# miniDCU.net
KiCad netlist of a schematic drawn in EAGLE
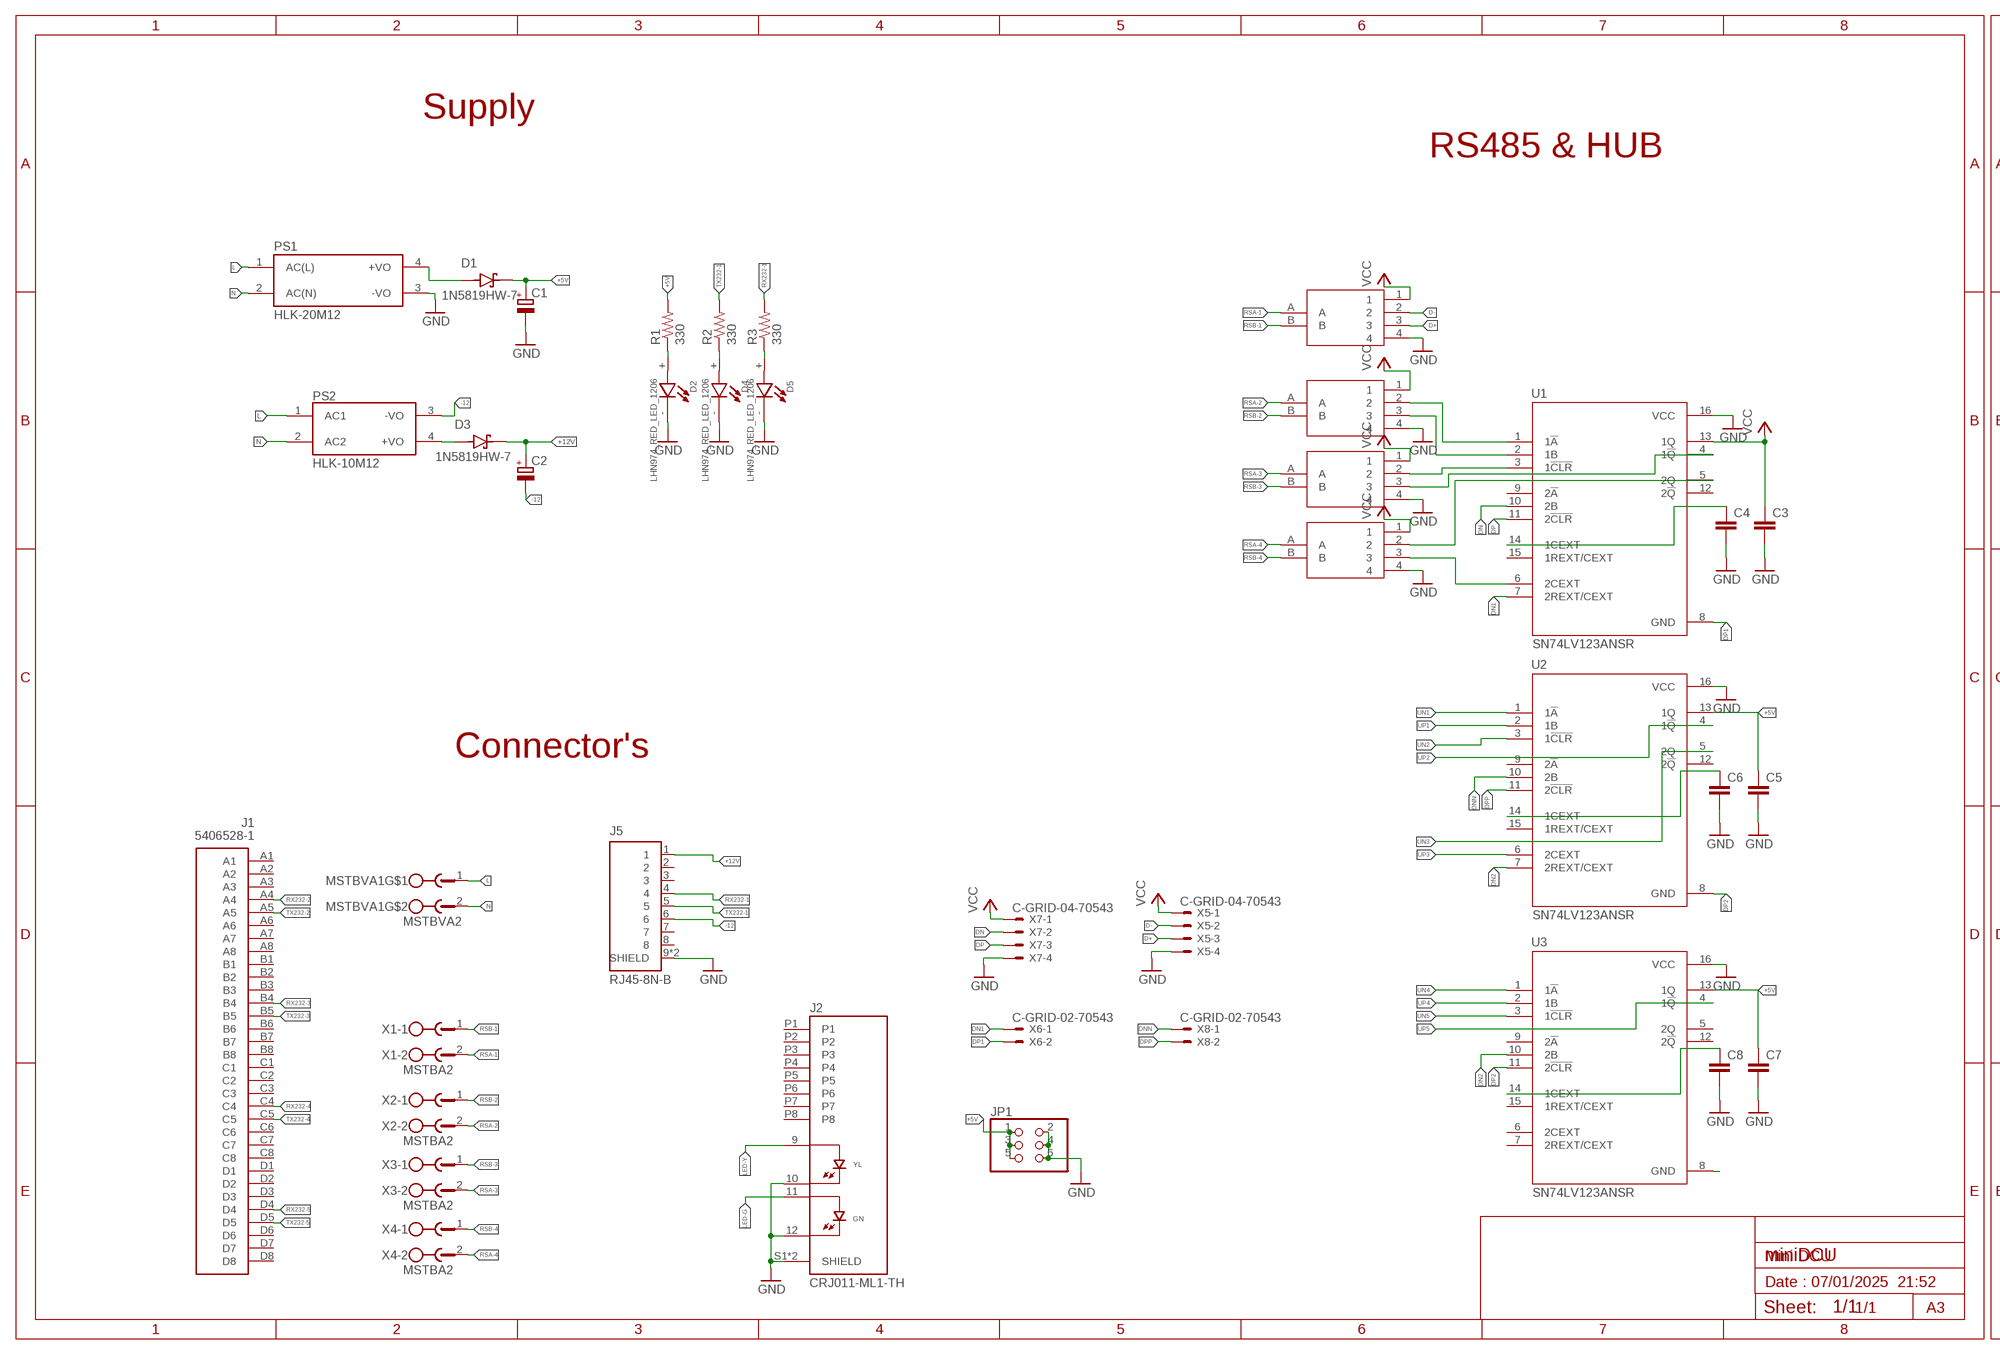
[diagram p0: schematic, sheet 1, part 1 of 2]
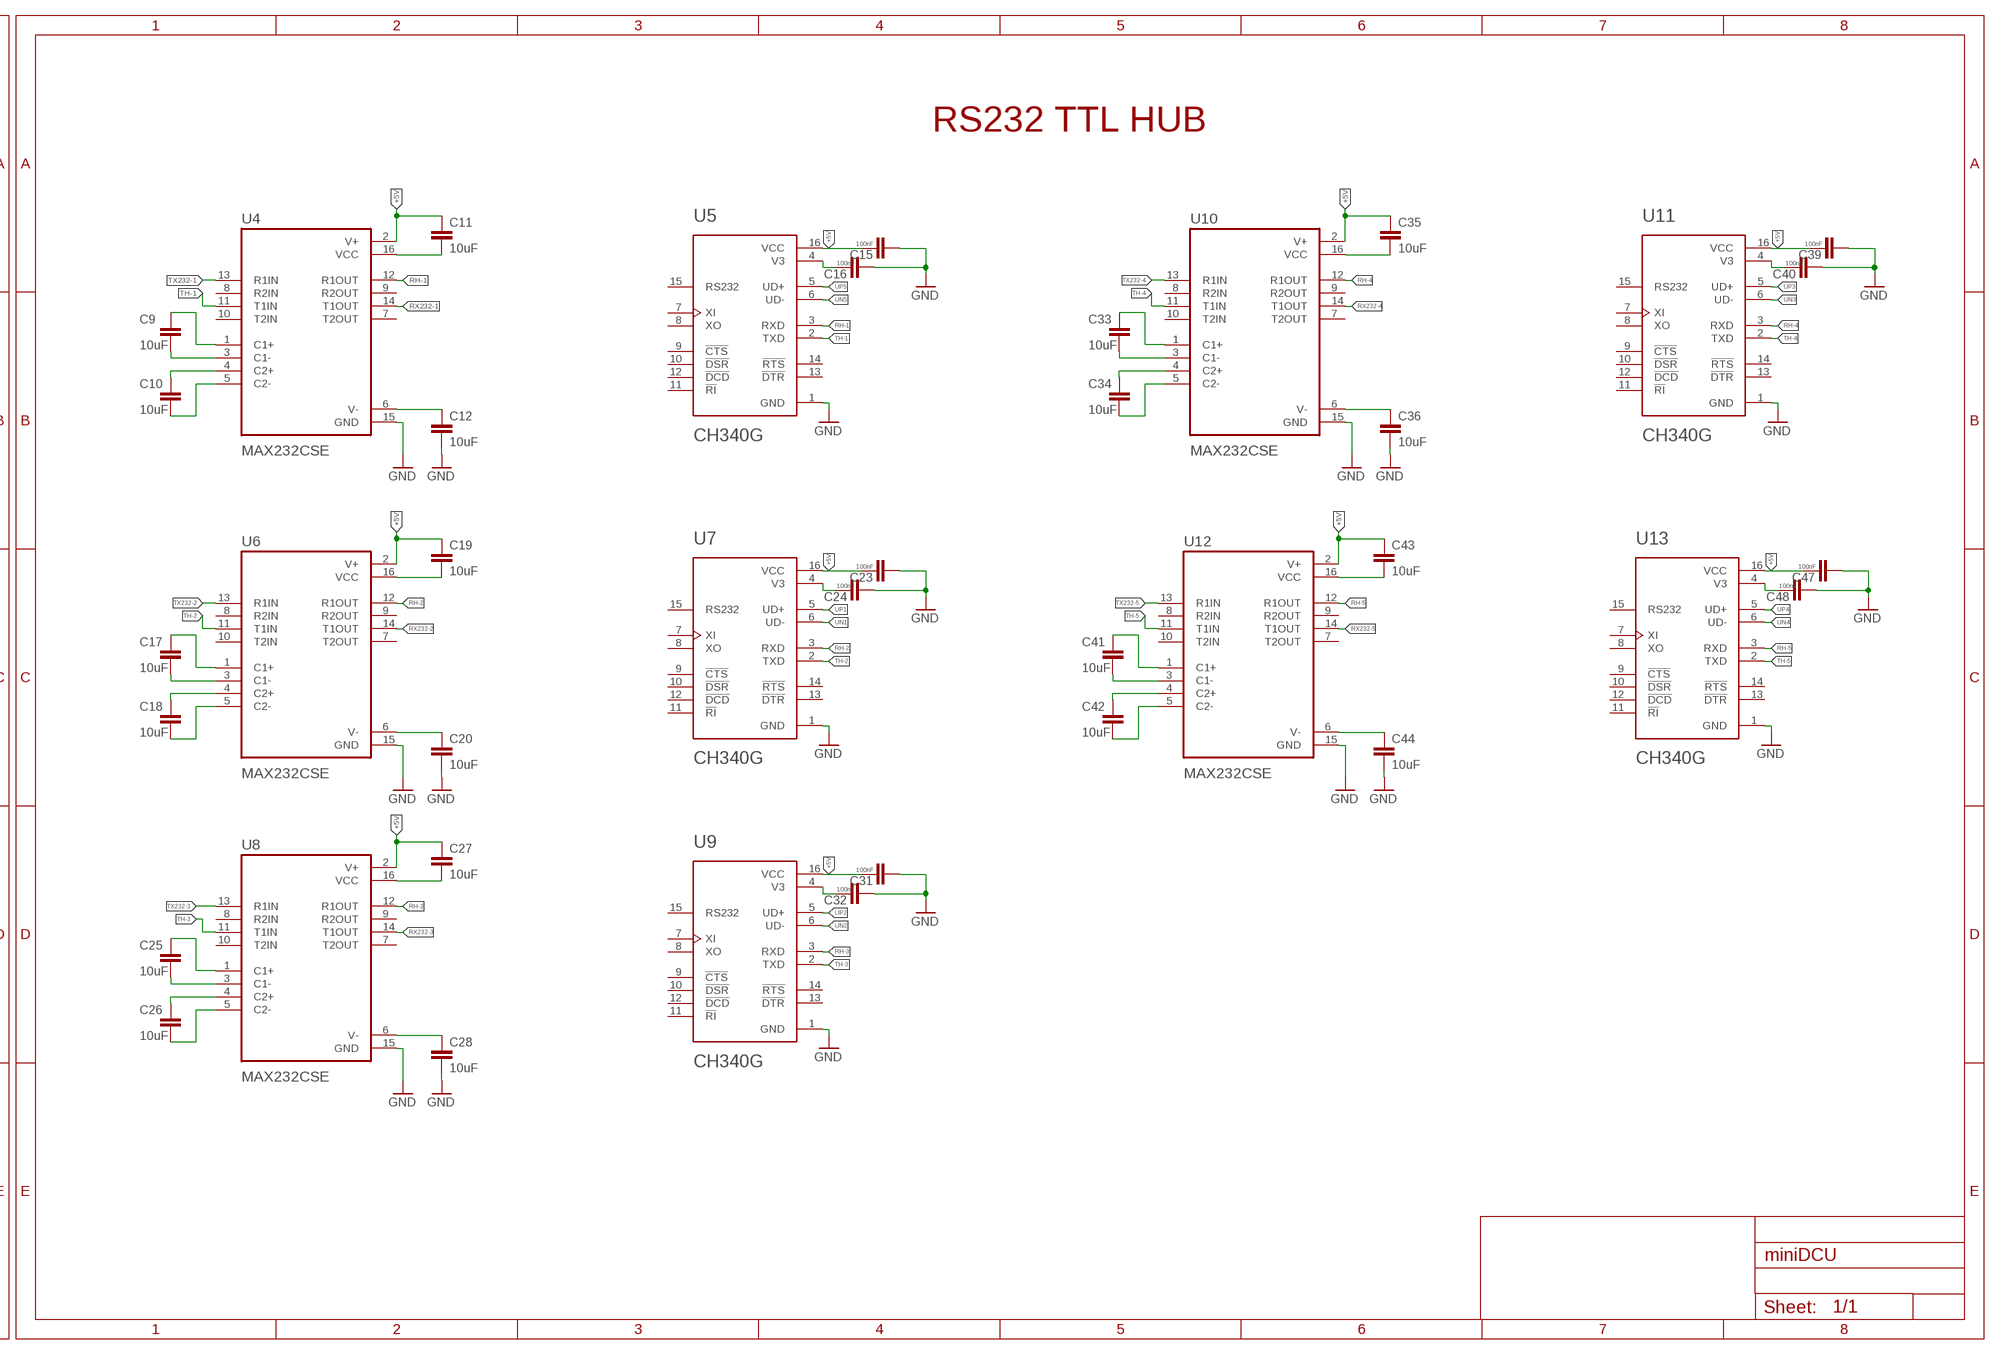
[diagram p1: schematic, sheet 1, part 2 of 2]

(export (version "E")
  (design (tool "Eeschema 10.0.6"))
  (components
    (comp (ref "C1")
      (value "CPOL-EU153CLV-0505")
      (footprint "eagle-import:153CLV-0505")
      (libsource (lib "eagle-import") (part "CPOL-EU153CLV-0505"))
    )
    (comp (ref "C2")
      (value "CPOL-EU153CLV-0505")
      (footprint "eagle-import:153CLV-0505")
      (libsource (lib "eagle-import") (part "CPOL-EU153CLV-0505"))
    )
    (comp (ref "C3")
      (value "C-EUC0603K")
      (footprint "eagle-import:C0603K")
      (libsource (lib "eagle-import") (part "C-EUC0603K"))
    )
    (comp (ref "C4")
      (value "C-EUC0603K")
      (footprint "eagle-import:C0603K")
      (libsource (lib "eagle-import") (part "C-EUC0603K"))
    )
    (comp (ref "C5")
      (value "C-EUC0603K")
      (footprint "eagle-import:C0603K")
      (libsource (lib "eagle-import") (part "C-EUC0603K"))
    )
    (comp (ref "C6")
      (value "C-EUC0603K")
      (footprint "eagle-import:C0603K")
      (libsource (lib "eagle-import") (part "C-EUC0603K"))
    )
    (comp (ref "C7")
      (value "C-EUC0603K")
      (footprint "eagle-import:C0603K")
      (libsource (lib "eagle-import") (part "C-EUC0603K"))
    )
    (comp (ref "C8")
      (value "C-EUC0603K")
      (footprint "eagle-import:C0603K")
      (libsource (lib "eagle-import") (part "C-EUC0603K"))
    )
    (comp (ref "C9")
      (value "10uF")
      (footprint "eagle-import:C0805")
      (libsource (lib "eagle-import") (part "C-EUC0805"))
    )
    (comp (ref "C10")
      (value "10uF")
      (footprint "eagle-import:C0805")
      (libsource (lib "eagle-import") (part "C-EUC0805"))
    )
    (comp (ref "C11")
      (value "10uF")
      (footprint "eagle-import:C0805")
      (libsource (lib "eagle-import") (part "C-EUC0805"))
    )
    (comp (ref "C12")
      (value "10uF")
      (footprint "eagle-import:C0805")
      (libsource (lib "eagle-import") (part "C-EUC0805"))
    )
    (comp (ref "C15")
      (value "100nF")
      (footprint "eagle-import:C0805K")
      (libsource (lib "eagle-import") (part "C-EUC0805K"))
    )
    (comp (ref "C16")
      (value "100nF")
      (footprint "eagle-import:C0805K")
      (libsource (lib "eagle-import") (part "C-EUC0805K"))
    )
    (comp (ref "C17")
      (value "10uF")
      (footprint "eagle-import:C0805")
      (libsource (lib "eagle-import") (part "C-EUC0805"))
    )
    (comp (ref "C18")
      (value "10uF")
      (footprint "eagle-import:C0805")
      (libsource (lib "eagle-import") (part "C-EUC0805"))
    )
    (comp (ref "C19")
      (value "10uF")
      (footprint "eagle-import:C0805")
      (libsource (lib "eagle-import") (part "C-EUC0805"))
    )
    (comp (ref "C20")
      (value "10uF")
      (footprint "eagle-import:C0805")
      (libsource (lib "eagle-import") (part "C-EUC0805"))
    )
    (comp (ref "C23")
      (value "100nF")
      (footprint "eagle-import:C0805K")
      (libsource (lib "eagle-import") (part "C-EUC0805K"))
    )
    (comp (ref "C24")
      (value "100nF")
      (footprint "eagle-import:C0805K")
      (libsource (lib "eagle-import") (part "C-EUC0805K"))
    )
    (comp (ref "C25")
      (value "10uF")
      (footprint "eagle-import:C0805")
      (libsource (lib "eagle-import") (part "C-EUC0805"))
    )
    (comp (ref "C26")
      (value "10uF")
      (footprint "eagle-import:C0805")
      (libsource (lib "eagle-import") (part "C-EUC0805"))
    )
    (comp (ref "C27")
      (value "10uF")
      (footprint "eagle-import:C0805")
      (libsource (lib "eagle-import") (part "C-EUC0805"))
    )
    (comp (ref "C28")
      (value "10uF")
      (footprint "eagle-import:C0805")
      (libsource (lib "eagle-import") (part "C-EUC0805"))
    )
    (comp (ref "C31")
      (value "100nF")
      (footprint "eagle-import:C0805K")
      (libsource (lib "eagle-import") (part "C-EUC0805K"))
    )
    (comp (ref "C32")
      (value "100nF")
      (footprint "eagle-import:C0805K")
      (libsource (lib "eagle-import") (part "C-EUC0805K"))
    )
    (comp (ref "C33")
      (value "10uF")
      (footprint "eagle-import:C0805")
      (libsource (lib "eagle-import") (part "C-EUC0805"))
    )
    (comp (ref "C34")
      (value "10uF")
      (footprint "eagle-import:C0805")
      (libsource (lib "eagle-import") (part "C-EUC0805"))
    )
    (comp (ref "C35")
      (value "10uF")
      (footprint "eagle-import:C0805")
      (libsource (lib "eagle-import") (part "C-EUC0805"))
    )
    (comp (ref "C36")
      (value "10uF")
      (footprint "eagle-import:C0805")
      (libsource (lib "eagle-import") (part "C-EUC0805"))
    )
    (comp (ref "C39")
      (value "100nF")
      (footprint "eagle-import:C0805K")
      (libsource (lib "eagle-import") (part "C-EUC0805K"))
    )
    (comp (ref "C40")
      (value "100nF")
      (footprint "eagle-import:C0805K")
      (libsource (lib "eagle-import") (part "C-EUC0805K"))
    )
    (comp (ref "C41")
      (value "10uF")
      (footprint "eagle-import:C0805")
      (libsource (lib "eagle-import") (part "C-EUC0805"))
    )
    (comp (ref "C42")
      (value "10uF")
      (footprint "eagle-import:C0805")
      (libsource (lib "eagle-import") (part "C-EUC0805"))
    )
    (comp (ref "C43")
      (value "10uF")
      (footprint "eagle-import:C0805")
      (libsource (lib "eagle-import") (part "C-EUC0805"))
    )
    (comp (ref "C44")
      (value "10uF")
      (footprint "eagle-import:C0805")
      (libsource (lib "eagle-import") (part "C-EUC0805"))
    )
    (comp (ref "C47")
      (value "100nF")
      (footprint "eagle-import:C0805K")
      (libsource (lib "eagle-import") (part "C-EUC0805K"))
    )
    (comp (ref "C48")
      (value "100nF")
      (footprint "eagle-import:C0805K")
      (libsource (lib "eagle-import") (part "C-EUC0805K"))
    )
    (comp (ref "D1")
      (value "1N5819HW-7")
      (footprint "eagle-import:SOD3715X145N")
      (fields (field (name "MF") "Diodes Inc."))
      (libsource (lib "eagle-import") (part "1N5819HW-7"))
    )
    (comp (ref "D2")
      (value "LHN974_RED_LED_1206")
      (footprint "eagle-import:LEDC3216X120N")
      (fields (field (name "MF") "Osram") (field (name "MP") "LHN974 RED LED 1206"))
      (libsource (lib "eagle-import") (part "LHN974_RED_LED_1206"))
    )
    (comp (ref "D3")
      (value "1N5819HW-7")
      (footprint "eagle-import:SOD3715X145N")
      (fields (field (name "MF") "Diodes Inc."))
      (libsource (lib "eagle-import") (part "1N5819HW-7"))
    )
    (comp (ref "D4")
      (value "LHN974_RED_LED_1206")
      (footprint "eagle-import:LEDC3216X120N")
      (fields (field (name "MF") "Osram") (field (name "MP") "LHN974 RED LED 1206"))
      (libsource (lib "eagle-import") (part "LHN974_RED_LED_1206"))
    )
    (comp (ref "D5")
      (value "LHN974_RED_LED_1206")
      (footprint "eagle-import:LEDC3216X120N")
      (fields (field (name "MF") "Osram") (field (name "MP") "LHN974 RED LED 1206"))
      (libsource (lib "eagle-import") (part "LHN974_RED_LED_1206"))
    )
    (comp (ref "J1")
      (value "5406528-1")
      (footprint "eagle-import:5406528-1")
      (fields (field (name "MF") "TE Connectivity"))
      (libsource (lib "eagle-import") (part "5406528-1"))
    )
    (comp (ref "J2")
      (value "CRJ011-ML1-TH")
      (footprint "eagle-import:CUI_CRJ011-ML1-TH")
      (fields (field (name "MF") "Same Sky"))
      (libsource (lib "eagle-import") (part "CRJ011-ML1-TH"))
    )
    (comp (ref "J5")
      (value "RJ45-8N-B")
      (footprint "eagle-import:TE_RJ45-8N-B")
      (fields (field (name "MF") "TE Connectivity"))
      (libsource (lib "eagle-import") (part "RJ45-8N-B"))
    )
    (comp (ref "JP1")
      (value "PINHD-2X3")
      (footprint "eagle-import:2X03")
      (libsource (lib "eagle-import") (part "PINHD-2X3"))
    )
    (comp (ref "MSTBVA1")
      (value "MSTBVA2")
      (footprint "eagle-import:MSTBVA2")
      (libsource (lib "eagle-import") (part "MSTBVA2"))
    )
    (comp (ref "PS1")
      (value "HLK-20M12")
      (footprint "eagle-import:CONV_HLK-20M12")
      (fields (field (name "MF") "Hi-link"))
      (libsource (lib "eagle-import") (part "HLK-20M12"))
    )
    (comp (ref "PS2")
      (value "HLK-10M12")
      (footprint "eagle-import:CONV_HLK-10M12")
      (fields (field (name "MF") "Hi-link"))
      (libsource (lib "eagle-import") (part "HLK-10M12"))
    )
    (comp (ref "R1")
      (value "330")
      (footprint "eagle-import:M0805")
      (libsource (lib "eagle-import") (part "R-US_M0805"))
    )
    (comp (ref "R2")
      (value "330")
      (footprint "eagle-import:M0805")
      (libsource (lib "eagle-import") (part "R-US_M0805"))
    )
    (comp (ref "R3")
      (value "330")
      (footprint "eagle-import:M0805")
      (libsource (lib "eagle-import") (part "R-US_M0805"))
    )
    (comp (ref "U1")
      (value "SN74LV123ANSR")
      (footprint "eagle-import:SOIC127P780X200-16N")
      (fields (field (name "DIGIKEY_PART_NUMBER") "296-46201-2-ND") (field (name "MF") "Texas Instruments"))
      (libsource (lib "eagle-import") (part "SN74LV123ANSR"))
    )
    (comp (ref "U2")
      (value "SN74LV123ANSR")
      (footprint "eagle-import:SOIC127P780X200-16N")
      (fields (field (name "DIGIKEY_PART_NUMBER") "296-46201-2-ND") (field (name "MF") "Texas Instruments"))
      (libsource (lib "eagle-import") (part "SN74LV123ANSR"))
    )
    (comp (ref "U3")
      (value "SN74LV123ANSR")
      (footprint "eagle-import:SOIC127P780X200-16N")
      (fields (field (name "DIGIKEY_PART_NUMBER") "296-46201-2-ND") (field (name "MF") "Texas Instruments"))
      (libsource (lib "eagle-import") (part "SN74LV123ANSR"))
    )
    (comp (ref "U4")
      (value "MAX232CSE")
      (footprint "eagle-import:SOIC127P600X175-16N")
      (fields (field (name "MF") "Maxim Integrated"))
      (libsource (lib "eagle-import") (part "MAX232CSE"))
    )
    (comp (ref "U5")
      (value "CH340G")
      (footprint "eagle-import:SOIC127P600X180-16N")
      (fields (field (name "MF") "WCH") (field (name "MP") "Ch340G"))
      (libsource (lib "eagle-import") (part "CH340G"))
    )
    (comp (ref "U6")
      (value "MAX232CSE")
      (footprint "eagle-import:SOIC127P600X175-16N")
      (fields (field (name "MF") "Maxim Integrated"))
      (libsource (lib "eagle-import") (part "MAX232CSE"))
    )
    (comp (ref "U7")
      (value "CH340G")
      (footprint "eagle-import:SOIC127P600X180-16N")
      (fields (field (name "MF") "WCH") (field (name "MP") "Ch340G"))
      (libsource (lib "eagle-import") (part "CH340G"))
    )
    (comp (ref "U8")
      (value "MAX232CSE")
      (footprint "eagle-import:SOIC127P600X175-16N")
      (fields (field (name "MF") "Maxim Integrated"))
      (libsource (lib "eagle-import") (part "MAX232CSE"))
    )
    (comp (ref "U9")
      (value "CH340G")
      (footprint "eagle-import:SOIC127P600X180-16N")
      (fields (field (name "MF") "WCH") (field (name "MP") "Ch340G"))
      (libsource (lib "eagle-import") (part "CH340G"))
    )
    (comp (ref "U10")
      (value "MAX232CSE")
      (footprint "eagle-import:SOIC127P600X175-16N")
      (fields (field (name "MF") "Maxim Integrated"))
      (libsource (lib "eagle-import") (part "MAX232CSE"))
    )
    (comp (ref "U11")
      (value "CH340G")
      (footprint "eagle-import:SOIC127P600X180-16N")
      (fields (field (name "MF") "WCH") (field (name "MP") "Ch340G"))
      (libsource (lib "eagle-import") (part "CH340G"))
    )
    (comp (ref "U12")
      (value "MAX232CSE")
      (footprint "eagle-import:SOIC127P600X175-16N")
      (fields (field (name "MF") "Maxim Integrated"))
      (libsource (lib "eagle-import") (part "MAX232CSE"))
    )
    (comp (ref "U13")
      (value "CH340G")
      (footprint "eagle-import:SOIC127P600X180-16N")
      (fields (field (name "MF") "WCH") (field (name "MP") "Ch340G"))
      (libsource (lib "eagle-import") (part "CH340G"))
    )
    (comp (ref "USB2RS1")
      (value "USB2RS485")
      (footprint "eagle-import:USB2RS485")
      (libsource (lib "eagle-import") (part "USB2RS485"))
    )
    (comp (ref "USB2RS2")
      (value "USB2RS485")
      (footprint "eagle-import:USB2RS485")
      (libsource (lib "eagle-import") (part "USB2RS485"))
    )
    (comp (ref "USB2RS3")
      (value "USB2RS485")
      (footprint "eagle-import:USB2RS485")
      (libsource (lib "eagle-import") (part "USB2RS485"))
    )
    (comp (ref "USB2RS5")
      (value "USB2RS485")
      (footprint "eagle-import:USB2RS485")
      (libsource (lib "eagle-import") (part "USB2RS485"))
    )
    (comp (ref "X1")
      (value "MSTBA2")
      (footprint "eagle-import:MSTBA2")
      (fields (field (name "MF") "FARNELL") (field (name "MPN") "1757242"))
      (libsource (lib "eagle-import") (part "MSTBA2"))
    )
    (comp (ref "X2")
      (value "MSTBA2")
      (footprint "eagle-import:MSTBA2")
      (fields (field (name "MF") "FARNELL") (field (name "MPN") "1757242"))
      (libsource (lib "eagle-import") (part "MSTBA2"))
    )
    (comp (ref "X3")
      (value "MSTBA2")
      (footprint "eagle-import:MSTBA2")
      (fields (field (name "MF") "FARNELL") (field (name "MPN") "1757242"))
      (libsource (lib "eagle-import") (part "MSTBA2"))
    )
    (comp (ref "X4")
      (value "MSTBA2")
      (footprint "eagle-import:MSTBA2")
      (fields (field (name "MF") "FARNELL") (field (name "MPN") "1757242"))
      (libsource (lib "eagle-import") (part "MSTBA2"))
    )
    (comp (ref "X5")
      (value "C-GRID-04-70543")
      (footprint "eagle-import:70543-04")
      (fields (field (name "MF") "MOLEX"))
      (libsource (lib "eagle-import") (part "C-GRID-04-70543"))
    )
    (comp (ref "X6")
      (value "C-GRID-02-70543")
      (footprint "eagle-import:70543-02")
      (fields (field (name "MF") "MOLEX"))
      (libsource (lib "eagle-import") (part "C-GRID-02-70543"))
    )
    (comp (ref "X7")
      (value "C-GRID-04-70543")
      (footprint "eagle-import:70543-04")
      (fields (field (name "MF") "MOLEX"))
      (libsource (lib "eagle-import") (part "C-GRID-04-70543"))
    )
    (comp (ref "X8")
      (value "C-GRID-02-70543")
      (footprint "eagle-import:70543-02")
      (fields (field (name "MF") "MOLEX"))
      (libsource (lib "eagle-import") (part "C-GRID-02-70543"))
    )
  )
  (nets
    (net (code "1") (name "+5V") (class "Default")
      (node (ref "C1") (pin "+") (pinfunction "+_+") (pintype "passive"))
      (node (ref "C11") (pin "1") (pinfunction "1_1") (pintype "passive"))
      (node (ref "C15") (pin "1") (pinfunction "1_1") (pintype "passive"))
      (node (ref "C19") (pin "1") (pinfunction "1_1") (pintype "passive"))
      (node (ref "C23") (pin "1") (pinfunction "1_1") (pintype "passive"))
      (node (ref "C27") (pin "1") (pinfunction "1_1") (pintype "passive"))
      (node (ref "C31") (pin "1") (pinfunction "1_1") (pintype "passive"))
      (node (ref "C35") (pin "1") (pinfunction "1_1") (pintype "passive"))
      (node (ref "C39") (pin "1") (pinfunction "1_1") (pintype "passive"))
      (node (ref "C43") (pin "1") (pinfunction "1_1") (pintype "passive"))
      (node (ref "C47") (pin "1") (pinfunction "1_1") (pintype "passive"))
      (node (ref "C5") (pin "1") (pinfunction "1_1") (pintype "passive"))
      (node (ref "C7") (pin "1") (pinfunction "1_1") (pintype "passive"))
      (node (ref "D1") (pin "C") (pinfunction "K_C") (pintype "passive"))
      (node (ref "JP1") (pin "1") (pinfunction "1_1") (pintype "passive"))
      (node (ref "JP1") (pin "3") (pinfunction "3_3") (pintype "passive"))
      (node (ref "JP1") (pin "5") (pinfunction "5_5") (pintype "passive"))
      (node (ref "R1") (pin "2") (pinfunction "2_2") (pintype "passive"))
      (node (ref "U10") (pin "2") (pinfunction "V+_2") (pintype "power_in"))
      (node (ref "U11") (pin "16") (pinfunction "VCC_16") (pintype "power_in"))
      (node (ref "U12") (pin "2") (pinfunction "V+_2") (pintype "power_in"))
      (node (ref "U13") (pin "16") (pinfunction "VCC_16") (pintype "power_in"))
      (node (ref "U2") (pin "13") (pinfunction "1Q_13") (pintype "output"))
      (node (ref "U3") (pin "13") (pinfunction "1Q_13") (pintype "output"))
      (node (ref "U4") (pin "2") (pinfunction "V+_2") (pintype "power_in"))
      (node (ref "U5") (pin "16") (pinfunction "VCC_16") (pintype "power_in"))
      (node (ref "U6") (pin "2") (pinfunction "V+_2") (pintype "power_in"))
      (node (ref "U7") (pin "16") (pinfunction "VCC_16") (pintype "power_in"))
      (node (ref "U8") (pin "2") (pinfunction "V+_2") (pintype "power_in"))
      (node (ref "U9") (pin "16") (pinfunction "VCC_16") (pintype "power_in"))
    )
    (net (code "2") (name "+12V") (class "Default")
      (node (ref "C2") (pin "+") (pinfunction "+_+") (pintype "passive"))
      (node (ref "D3") (pin "C") (pinfunction "K_C") (pintype "passive"))
      (node (ref "J5") (pin "1") (pinfunction "1_1") (pintype "passive"))
    )
    (net (code "3") (name "-12") (class "Default")
      (node (ref "C2") (pin "-") (pinfunction "-_-") (pintype "passive"))
      (node (ref "J5") (pin "6") (pinfunction "6_6") (pintype "passive"))
      (node (ref "PS2") (pin "3") (pinfunction "-VO_3") (pintype "output"))
    )
    (net (code "4") (name "D+") (class "Default")
      (node (ref "USB2RS5") (pin "3") (pinfunction "3_3") (pintype "bidirectional"))
      (node (ref "X5") (pin "3") (pinfunction "S_3") (pintype "passive"))
    )
    (net (code "5") (name "D-") (class "Default")
      (node (ref "USB2RS5") (pin "2") (pinfunction "2_2") (pintype "bidirectional"))
      (node (ref "X5") (pin "2") (pinfunction "S_2") (pintype "passive"))
    )
    (net (code "6") (name "DN") (class "Default")
      (node (ref "U1") (pin "10") (pinfunction "2B_10") (pintype "input"))
      (node (ref "X7") (pin "2") (pinfunction "S_2") (pintype "passive"))
    )
    (net (code "7") (name "DN1") (class "Default")
      (node (ref "U1") (pin "7") (pinfunction "2REXT/CEXT_7") (pintype "bidirectional"))
      (node (ref "X6") (pin "1") (pinfunction "S_1") (pintype "passive"))
    )
    (net (code "8") (name "DN2") (class "Default")
      (node (ref "U2") (pin "7") (pinfunction "2REXT/CEXT_7") (pintype "bidirectional"))
      (node (ref "U3") (pin "10") (pinfunction "2B_10") (pintype "input"))
    )
    (net (code "9") (name "DNN") (class "Default")
      (node (ref "U2") (pin "10") (pinfunction "2B_10") (pintype "input"))
      (node (ref "X8") (pin "1") (pinfunction "S_1") (pintype "passive"))
    )
    (net (code "10") (name "DP") (class "Default")
      (node (ref "U1") (pin "11") (pinfunction "2~{CLR}_11") (pintype "input"))
      (node (ref "X7") (pin "3") (pinfunction "S_3") (pintype "passive"))
    )
    (net (code "11") (name "DP1") (class "Default")
      (node (ref "U1") (pin "8") (pinfunction "GND_8") (pintype "power_in"))
      (node (ref "X6") (pin "2") (pinfunction "S_2") (pintype "passive"))
    )
    (net (code "12") (name "DP2") (class "Default")
      (node (ref "U2") (pin "8") (pinfunction "GND_8") (pintype "power_in"))
      (node (ref "U3") (pin "11") (pinfunction "2~{CLR}_11") (pintype "input"))
    )
    (net (code "13") (name "DPP") (class "Default")
      (node (ref "U2") (pin "11") (pinfunction "2~{CLR}_11") (pintype "input"))
      (node (ref "X8") (pin "2") (pinfunction "S_2") (pintype "passive"))
    )
    (net (code "14") (name "GND") (class "Default")
      (node (ref "C1") (pin "-") (pinfunction "-_-") (pintype "passive"))
      (node (ref "C12") (pin "2") (pinfunction "2_2") (pintype "passive"))
      (node (ref "C15") (pin "2") (pinfunction "2_2") (pintype "passive"))
      (node (ref "C16") (pin "2") (pinfunction "2_2") (pintype "passive"))
      (node (ref "C20") (pin "2") (pinfunction "2_2") (pintype "passive"))
      (node (ref "C23") (pin "2") (pinfunction "2_2") (pintype "passive"))
      (node (ref "C24") (pin "2") (pinfunction "2_2") (pintype "passive"))
      (node (ref "C28") (pin "2") (pinfunction "2_2") (pintype "passive"))
      (node (ref "C3") (pin "2") (pinfunction "2_2") (pintype "passive"))
      (node (ref "C31") (pin "2") (pinfunction "2_2") (pintype "passive"))
      (node (ref "C32") (pin "2") (pinfunction "2_2") (pintype "passive"))
      (node (ref "C36") (pin "2") (pinfunction "2_2") (pintype "passive"))
      (node (ref "C39") (pin "2") (pinfunction "2_2") (pintype "passive"))
      (node (ref "C4") (pin "2") (pinfunction "2_2") (pintype "passive"))
      (node (ref "C40") (pin "2") (pinfunction "2_2") (pintype "passive"))
      (node (ref "C44") (pin "2") (pinfunction "2_2") (pintype "passive"))
      (node (ref "C47") (pin "2") (pinfunction "2_2") (pintype "passive"))
      (node (ref "C48") (pin "2") (pinfunction "2_2") (pintype "passive"))
      (node (ref "C5") (pin "2") (pinfunction "2_2") (pintype "passive"))
      (node (ref "C6") (pin "2") (pinfunction "2_2") (pintype "passive"))
      (node (ref "C7") (pin "2") (pinfunction "2_2") (pintype "passive"))
      (node (ref "C8") (pin "2") (pinfunction "2_2") (pintype "passive"))
      (node (ref "D2") (pin "-") (pinfunction "-_-") (pintype "passive"))
      (node (ref "D4") (pin "-") (pinfunction "-_-") (pintype "passive"))
      (node (ref "D5") (pin "-") (pinfunction "-_-") (pintype "passive"))
      (node (ref "J2") (pin "10") (pinfunction "10_10") (pintype "passive"))
      (node (ref "J2") (pin "12") (pinfunction "12_12") (pintype "passive"))
      (node (ref "J2") (pin "S1") (pinfunction "SHIELD_S1") (pintype "passive"))
      (node (ref "J2") (pin "S2") (pinfunction "SHIELD_S2") (pintype "passive"))
      (node (ref "J5") (pin "10") (pinfunction "SHIELD_10") (pintype "passive"))
      (node (ref "J5") (pin "9") (pinfunction "SHIELD_9") (pintype "passive"))
      (node (ref "JP1") (pin "2") (pinfunction "2_2") (pintype "passive"))
      (node (ref "JP1") (pin "4") (pinfunction "4_4") (pintype "passive"))
      (node (ref "JP1") (pin "6") (pinfunction "6_6") (pintype "passive"))
      (node (ref "PS1") (pin "3") (pinfunction "-VO_3") (pintype "output"))
      (node (ref "U1") (pin "16") (pinfunction "VCC_16") (pintype "power_in"))
      (node (ref "U10") (pin "15") (pinfunction "GND_15") (pintype "power_in"))
      (node (ref "U11") (pin "1") (pinfunction "GND_1") (pintype "power_in"))
      (node (ref "U12") (pin "15") (pinfunction "GND_15") (pintype "power_in"))
      (node (ref "U13") (pin "1") (pinfunction "GND_1") (pintype "power_in"))
      (node (ref "U2") (pin "16") (pinfunction "VCC_16") (pintype "power_in"))
      (node (ref "U3") (pin "16") (pinfunction "VCC_16") (pintype "power_in"))
      (node (ref "U4") (pin "15") (pinfunction "GND_15") (pintype "power_in"))
      (node (ref "U5") (pin "1") (pinfunction "GND_1") (pintype "power_in"))
      (node (ref "U6") (pin "15") (pinfunction "GND_15") (pintype "power_in"))
      (node (ref "U7") (pin "1") (pinfunction "GND_1") (pintype "power_in"))
      (node (ref "U8") (pin "15") (pinfunction "GND_15") (pintype "power_in"))
      (node (ref "U9") (pin "1") (pinfunction "GND_1") (pintype "power_in"))
      (node (ref "USB2RS1") (pin "4") (pinfunction "4_4") (pintype "bidirectional"))
      (node (ref "USB2RS2") (pin "4") (pinfunction "4_4") (pintype "bidirectional"))
      (node (ref "USB2RS3") (pin "4") (pinfunction "4_4") (pintype "bidirectional"))
      (node (ref "USB2RS5") (pin "4") (pinfunction "4_4") (pintype "bidirectional"))
      (node (ref "X5") (pin "4") (pinfunction "S_4") (pintype "passive"))
      (node (ref "X7") (pin "4") (pinfunction "S_4") (pintype "passive"))
    )
    (net (code "15") (name "L") (class "Default")
      (node (ref "MSTBVA1") (pin "1") (pinfunction "1_1") (pintype "passive"))
      (node (ref "PS1") (pin "1") (pinfunction "AC(L)_1") (pintype "input"))
      (node (ref "PS2") (pin "1") (pinfunction "AC1_1") (pintype "input"))
    )
    (net (code "16") (name "LED-G") (class "Default")
      (node (ref "J2") (pin "11") (pinfunction "11_11") (pintype "passive"))
    )
    (net (code "17") (name "LED-Y") (class "Default")
      (node (ref "J2") (pin "9") (pinfunction "9_9") (pintype "passive"))
    )
    (net (code "18") (name "N") (class "Default")
      (node (ref "MSTBVA1") (pin "2") (pinfunction "1_2") (pintype "passive"))
      (node (ref "PS1") (pin "2") (pinfunction "AC(N)_2") (pintype "input"))
      (node (ref "PS2") (pin "2") (pinfunction "AC2_2") (pintype "input"))
    )
    (net (code "19") (name "Net-(D2-Pad+)") (class "Default")
      (node (ref "D2") (pin "+") (pinfunction "+_+") (pintype "passive"))
      (node (ref "R1") (pin "1") (pinfunction "1_1") (pintype "passive"))
    )
    (net (code "20") (name "Net-(D4-Pad+)") (class "Default")
      (node (ref "D4") (pin "+") (pinfunction "+_+") (pintype "passive"))
      (node (ref "R2") (pin "1") (pinfunction "1_1") (pintype "passive"))
    )
    (net (code "21") (name "Net-(D5-Pad+)") (class "Default")
      (node (ref "D5") (pin "+") (pinfunction "+_+") (pintype "passive"))
      (node (ref "R3") (pin "1") (pinfunction "1_1") (pintype "passive"))
    )
    (net (code "22") (name "Net-(PS1-+VO)") (class "Default")
      (node (ref "D1") (pin "A") (pinfunction "A_A") (pintype "passive"))
      (node (ref "PS1") (pin "4") (pinfunction "+VO_4") (pintype "output"))
    )
    (net (code "23") (name "Net-(PS2-+VO)") (class "Default")
      (node (ref "D3") (pin "A") (pinfunction "A_A") (pintype "passive"))
      (node (ref "PS2") (pin "4") (pinfunction "+VO_4") (pintype "output"))
    )
    (net (code "24") (name "Net-(U1-1B)") (class "Default")
      (node (ref "U1") (pin "2") (pinfunction "1B_2") (pintype "input"))
      (node (ref "USB2RS1") (pin "3") (pinfunction "3_3") (pintype "bidirectional"))
    )
    (net (code "25") (name "Net-(U1-1CEXT)") (class "Default")
      (node (ref "C4") (pin "1") (pinfunction "1_1") (pintype "passive"))
      (node (ref "U1") (pin "14") (pinfunction "1CEXT_14") (pintype "bidirectional"))
    )
    (net (code "26") (name "Net-(U1-1~{A})") (class "Default")
      (node (ref "U1") (pin "1") (pinfunction "1~{A}_1") (pintype "input"))
      (node (ref "USB2RS1") (pin "2") (pinfunction "2_2") (pintype "bidirectional"))
    )
    (net (code "27") (name "Net-(U1-1~{CLR})") (class "Default")
      (node (ref "U1") (pin "3") (pinfunction "1~{CLR}_3") (pintype "input"))
      (node (ref "USB2RS2") (pin "2") (pinfunction "2_2") (pintype "bidirectional"))
    )
    (net (code "28") (name "Net-(U1-1~{Q})") (class "Default")
      (node (ref "U1") (pin "4") (pinfunction "1~{Q}_4") (pintype "output"))
      (node (ref "USB2RS2") (pin "3") (pinfunction "3_3") (pintype "bidirectional"))
    )
    (net (code "29") (name "Net-(U1-2CEXT)") (class "Default")
      (node (ref "U1") (pin "6") (pinfunction "2CEXT_6") (pintype "bidirectional"))
      (node (ref "USB2RS3") (pin "3") (pinfunction "3_3") (pintype "bidirectional"))
    )
    (net (code "30") (name "Net-(U1-2Q)") (class "Default")
      (node (ref "U1") (pin "5") (pinfunction "2Q_5") (pintype "output"))
      (node (ref "USB2RS3") (pin "2") (pinfunction "2_2") (pintype "bidirectional"))
    )
    (net (code "31") (name "Net-(U2-1CEXT)") (class "Default")
      (node (ref "C6") (pin "1") (pinfunction "1_1") (pintype "passive"))
      (node (ref "U2") (pin "14") (pinfunction "1CEXT_14") (pintype "bidirectional"))
    )
    (net (code "32") (name "Net-(U3-1CEXT)") (class "Default")
      (node (ref "C8") (pin "1") (pinfunction "1_1") (pintype "passive"))
      (node (ref "U3") (pin "14") (pinfunction "1CEXT_14") (pintype "bidirectional"))
    )
    (net (code "33") (name "Net-(U4-C1+)") (class "Default")
      (node (ref "C9") (pin "1") (pinfunction "1_1") (pintype "passive"))
      (node (ref "U4") (pin "1") (pinfunction "C1+_1") (pintype "bidirectional"))
    )
    (net (code "34") (name "Net-(U4-C1-)") (class "Default")
      (node (ref "C9") (pin "2") (pinfunction "2_2") (pintype "passive"))
      (node (ref "U4") (pin "3") (pinfunction "C1-_3") (pintype "bidirectional"))
    )
    (net (code "35") (name "Net-(U4-C2+)") (class "Default")
      (node (ref "C10") (pin "1") (pinfunction "1_1") (pintype "passive"))
      (node (ref "U4") (pin "4") (pinfunction "C2+_4") (pintype "bidirectional"))
    )
    (net (code "36") (name "Net-(U4-C2-)") (class "Default")
      (node (ref "C10") (pin "2") (pinfunction "2_2") (pintype "passive"))
      (node (ref "U4") (pin "5") (pinfunction "C2-_5") (pintype "bidirectional"))
    )
    (net (code "37") (name "Net-(U4-V-)") (class "Default")
      (node (ref "C12") (pin "1") (pinfunction "1_1") (pintype "passive"))
      (node (ref "U4") (pin "6") (pinfunction "V-_6") (pintype "power_in"))
    )
    (net (code "38") (name "Net-(U4-VCC)") (class "Default")
      (node (ref "C11") (pin "2") (pinfunction "2_2") (pintype "passive"))
      (node (ref "U4") (pin "16") (pinfunction "VCC_16") (pintype "power_in"))
    )
    (net (code "39") (name "Net-(U5-V3)") (class "Default")
      (node (ref "C16") (pin "1") (pinfunction "1_1") (pintype "passive"))
      (node (ref "U5") (pin "4") (pinfunction "V3_4") (pintype "power_in"))
    )
    (net (code "40") (name "Net-(U6-C1+)") (class "Default")
      (node (ref "C17") (pin "1") (pinfunction "1_1") (pintype "passive"))
      (node (ref "U6") (pin "1") (pinfunction "C1+_1") (pintype "bidirectional"))
    )
    (net (code "41") (name "Net-(U6-C1-)") (class "Default")
      (node (ref "C17") (pin "2") (pinfunction "2_2") (pintype "passive"))
      (node (ref "U6") (pin "3") (pinfunction "C1-_3") (pintype "bidirectional"))
    )
    (net (code "42") (name "Net-(U6-C2+)") (class "Default")
      (node (ref "C18") (pin "1") (pinfunction "1_1") (pintype "passive"))
      (node (ref "U6") (pin "4") (pinfunction "C2+_4") (pintype "bidirectional"))
    )
    (net (code "43") (name "Net-(U6-C2-)") (class "Default")
      (node (ref "C18") (pin "2") (pinfunction "2_2") (pintype "passive"))
      (node (ref "U6") (pin "5") (pinfunction "C2-_5") (pintype "bidirectional"))
    )
    (net (code "44") (name "Net-(U6-V-)") (class "Default")
      (node (ref "C20") (pin "1") (pinfunction "1_1") (pintype "passive"))
      (node (ref "U6") (pin "6") (pinfunction "V-_6") (pintype "power_in"))
    )
    (net (code "45") (name "Net-(U6-VCC)") (class "Default")
      (node (ref "C19") (pin "2") (pinfunction "2_2") (pintype "passive"))
      (node (ref "U6") (pin "16") (pinfunction "VCC_16") (pintype "power_in"))
    )
    (net (code "46") (name "Net-(U7-V3)") (class "Default")
      (node (ref "C24") (pin "1") (pinfunction "1_1") (pintype "passive"))
      (node (ref "U7") (pin "4") (pinfunction "V3_4") (pintype "power_in"))
    )
    (net (code "47") (name "Net-(U8-C1+)") (class "Default")
      (node (ref "C25") (pin "1") (pinfunction "1_1") (pintype "passive"))
      (node (ref "U8") (pin "1") (pinfunction "C1+_1") (pintype "bidirectional"))
    )
    (net (code "48") (name "Net-(U8-C1-)") (class "Default")
      (node (ref "C25") (pin "2") (pinfunction "2_2") (pintype "passive"))
      (node (ref "U8") (pin "3") (pinfunction "C1-_3") (pintype "bidirectional"))
    )
    (net (code "49") (name "Net-(U8-C2+)") (class "Default")
      (node (ref "C26") (pin "1") (pinfunction "1_1") (pintype "passive"))
      (node (ref "U8") (pin "4") (pinfunction "C2+_4") (pintype "bidirectional"))
    )
    (net (code "50") (name "Net-(U8-C2-)") (class "Default")
      (node (ref "C26") (pin "2") (pinfunction "2_2") (pintype "passive"))
      (node (ref "U8") (pin "5") (pinfunction "C2-_5") (pintype "bidirectional"))
    )
    (net (code "51") (name "Net-(U8-V-)") (class "Default")
      (node (ref "C28") (pin "1") (pinfunction "1_1") (pintype "passive"))
      (node (ref "U8") (pin "6") (pinfunction "V-_6") (pintype "power_in"))
    )
    (net (code "52") (name "Net-(U8-VCC)") (class "Default")
      (node (ref "C27") (pin "2") (pinfunction "2_2") (pintype "passive"))
      (node (ref "U8") (pin "16") (pinfunction "VCC_16") (pintype "power_in"))
    )
    (net (code "53") (name "Net-(U9-V3)") (class "Default")
      (node (ref "C32") (pin "1") (pinfunction "1_1") (pintype "passive"))
      (node (ref "U9") (pin "4") (pinfunction "V3_4") (pintype "power_in"))
    )
    (net (code "54") (name "Net-(U10-C1+)") (class "Default")
      (node (ref "C33") (pin "1") (pinfunction "1_1") (pintype "passive"))
      (node (ref "U10") (pin "1") (pinfunction "C1+_1") (pintype "bidirectional"))
    )
    (net (code "55") (name "Net-(U10-C1-)") (class "Default")
      (node (ref "C33") (pin "2") (pinfunction "2_2") (pintype "passive"))
      (node (ref "U10") (pin "3") (pinfunction "C1-_3") (pintype "bidirectional"))
    )
    (net (code "56") (name "Net-(U10-C2+)") (class "Default")
      (node (ref "C34") (pin "1") (pinfunction "1_1") (pintype "passive"))
      (node (ref "U10") (pin "4") (pinfunction "C2+_4") (pintype "bidirectional"))
    )
    (net (code "57") (name "Net-(U10-C2-)") (class "Default")
      (node (ref "C34") (pin "2") (pinfunction "2_2") (pintype "passive"))
      (node (ref "U10") (pin "5") (pinfunction "C2-_5") (pintype "bidirectional"))
    )
    (net (code "58") (name "Net-(U10-V-)") (class "Default")
      (node (ref "C36") (pin "1") (pinfunction "1_1") (pintype "passive"))
      (node (ref "U10") (pin "6") (pinfunction "V-_6") (pintype "power_in"))
    )
    (net (code "59") (name "Net-(U10-VCC)") (class "Default")
      (node (ref "C35") (pin "2") (pinfunction "2_2") (pintype "passive"))
      (node (ref "U10") (pin "16") (pinfunction "VCC_16") (pintype "power_in"))
    )
    (net (code "60") (name "Net-(U11-V3)") (class "Default")
      (node (ref "C40") (pin "1") (pinfunction "1_1") (pintype "passive"))
      (node (ref "U11") (pin "4") (pinfunction "V3_4") (pintype "power_in"))
    )
    (net (code "61") (name "Net-(U12-C1+)") (class "Default")
      (node (ref "C41") (pin "1") (pinfunction "1_1") (pintype "passive"))
      (node (ref "U12") (pin "1") (pinfunction "C1+_1") (pintype "bidirectional"))
    )
    (net (code "62") (name "Net-(U12-C1-)") (class "Default")
      (node (ref "C41") (pin "2") (pinfunction "2_2") (pintype "passive"))
      (node (ref "U12") (pin "3") (pinfunction "C1-_3") (pintype "bidirectional"))
    )
    (net (code "63") (name "Net-(U12-C2+)") (class "Default")
      (node (ref "C42") (pin "1") (pinfunction "1_1") (pintype "passive"))
      (node (ref "U12") (pin "4") (pinfunction "C2+_4") (pintype "bidirectional"))
    )
    (net (code "64") (name "Net-(U12-C2-)") (class "Default")
      (node (ref "C42") (pin "2") (pinfunction "2_2") (pintype "passive"))
      (node (ref "U12") (pin "5") (pinfunction "C2-_5") (pintype "bidirectional"))
    )
    (net (code "65") (name "Net-(U12-V-)") (class "Default")
      (node (ref "C44") (pin "1") (pinfunction "1_1") (pintype "passive"))
      (node (ref "U12") (pin "6") (pinfunction "V-_6") (pintype "power_in"))
    )
    (net (code "66") (name "Net-(U12-VCC)") (class "Default")
      (node (ref "C43") (pin "2") (pinfunction "2_2") (pintype "passive"))
      (node (ref "U12") (pin "16") (pinfunction "VCC_16") (pintype "power_in"))
    )
    (net (code "67") (name "Net-(U13-V3)") (class "Default")
      (node (ref "C48") (pin "1") (pinfunction "1_1") (pintype "passive"))
      (node (ref "U13") (pin "4") (pinfunction "V3_4") (pintype "power_in"))
    )
    (net (code "68") (name "RH-1") (class "Default")
      (node (ref "U4") (pin "12") (pinfunction "R1OUT_12") (pintype "output"))
      (node (ref "U5") (pin "3") (pinfunction "RXD_3") (pintype "input"))
    )
    (net (code "69") (name "RH-2") (class "Default")
      (node (ref "U6") (pin "12") (pinfunction "R1OUT_12") (pintype "output"))
      (node (ref "U7") (pin "3") (pinfunction "RXD_3") (pintype "input"))
    )
    (net (code "70") (name "RH-3") (class "Default")
      (node (ref "U8") (pin "12") (pinfunction "R1OUT_12") (pintype "output"))
      (node (ref "U9") (pin "3") (pinfunction "RXD_3") (pintype "input"))
    )
    (net (code "71") (name "RH-4") (class "Default")
      (node (ref "U10") (pin "12") (pinfunction "R1OUT_12") (pintype "output"))
      (node (ref "U11") (pin "3") (pinfunction "RXD_3") (pintype "input"))
    )
    (net (code "72") (name "RH-5") (class "Default")
      (node (ref "U12") (pin "12") (pinfunction "R1OUT_12") (pintype "output"))
      (node (ref "U13") (pin "3") (pinfunction "RXD_3") (pintype "input"))
    )
    (net (code "73") (name "RSA-1") (class "Default")
      (node (ref "USB2RS5") (pin "A") (pinfunction "A_A") (pintype "bidirectional"))
      (node (ref "X1") (pin "2") (pinfunction "1_2") (pintype "passive"))
    )
    (net (code "74") (name "RSA-2") (class "Default")
      (node (ref "USB2RS1") (pin "A") (pinfunction "A_A") (pintype "bidirectional"))
      (node (ref "X2") (pin "2") (pinfunction "1_2") (pintype "passive"))
    )
    (net (code "75") (name "RSA-3") (class "Default")
      (node (ref "USB2RS2") (pin "A") (pinfunction "A_A") (pintype "bidirectional"))
      (node (ref "X3") (pin "2") (pinfunction "1_2") (pintype "passive"))
    )
    (net (code "76") (name "RSA-4") (class "Default")
      (node (ref "USB2RS3") (pin "A") (pinfunction "A_A") (pintype "bidirectional"))
      (node (ref "X4") (pin "2") (pinfunction "1_2") (pintype "passive"))
    )
    (net (code "77") (name "RSB-1") (class "Default")
      (node (ref "USB2RS5") (pin "B") (pinfunction "B_B") (pintype "bidirectional"))
      (node (ref "X1") (pin "1") (pinfunction "1_1") (pintype "passive"))
    )
    (net (code "78") (name "RSB-2") (class "Default")
      (node (ref "USB2RS1") (pin "B") (pinfunction "B_B") (pintype "bidirectional"))
      (node (ref "X2") (pin "1") (pinfunction "1_1") (pintype "passive"))
    )
    (net (code "79") (name "RSB-3") (class "Default")
      (node (ref "USB2RS2") (pin "B") (pinfunction "B_B") (pintype "bidirectional"))
      (node (ref "X3") (pin "1") (pinfunction "1_1") (pintype "passive"))
    )
    (net (code "80") (name "RSB-4") (class "Default")
      (node (ref "USB2RS3") (pin "B") (pinfunction "B_B") (pintype "bidirectional"))
      (node (ref "X4") (pin "1") (pinfunction "1_1") (pintype "passive"))
    )
    (net (code "81") (name "RX232-1") (class "Default")
      (node (ref "J5") (pin "4") (pinfunction "4_4") (pintype "passive"))
      (node (ref "R3") (pin "2") (pinfunction "2_2") (pintype "passive"))
      (node (ref "U4") (pin "14") (pinfunction "T1OUT_14") (pintype "output"))
    )
    (net (code "82") (name "RX232-2") (class "Default")
      (node (ref "J1") (pin "A4") (pinfunction "A4_A4") (pintype "bidirectional"))
      (node (ref "U6") (pin "14") (pinfunction "T1OUT_14") (pintype "output"))
    )
    (net (code "83") (name "RX232-3") (class "Default")
      (node (ref "J1") (pin "B4") (pinfunction "B4_B4") (pintype "bidirectional"))
      (node (ref "U8") (pin "14") (pinfunction "T1OUT_14") (pintype "output"))
    )
    (net (code "84") (name "RX232-4") (class "Default")
      (node (ref "J1") (pin "C4") (pinfunction "C4_C4") (pintype "bidirectional"))
      (node (ref "U10") (pin "14") (pinfunction "T1OUT_14") (pintype "output"))
    )
    (net (code "85") (name "RX232-5") (class "Default")
      (node (ref "J1") (pin "D4") (pinfunction "D4_D4") (pintype "bidirectional"))
      (node (ref "U12") (pin "14") (pinfunction "T1OUT_14") (pintype "output"))
    )
    (net (code "86") (name "TH-1") (class "Default")
      (node (ref "U4") (pin "11") (pinfunction "T1IN_11") (pintype "input"))
      (node (ref "U5") (pin "2") (pinfunction "TXD_2") (pintype "output"))
    )
    (net (code "87") (name "TH-2") (class "Default")
      (node (ref "U6") (pin "11") (pinfunction "T1IN_11") (pintype "input"))
      (node (ref "U7") (pin "2") (pinfunction "TXD_2") (pintype "output"))
    )
    (net (code "88") (name "TH-3") (class "Default")
      (node (ref "U8") (pin "11") (pinfunction "T1IN_11") (pintype "input"))
      (node (ref "U9") (pin "2") (pinfunction "TXD_2") (pintype "output"))
    )
    (net (code "89") (name "TH-4") (class "Default")
      (node (ref "U10") (pin "11") (pinfunction "T1IN_11") (pintype "input"))
      (node (ref "U11") (pin "2") (pinfunction "TXD_2") (pintype "output"))
    )
    (net (code "90") (name "TH-5") (class "Default")
      (node (ref "U12") (pin "11") (pinfunction "T1IN_11") (pintype "input"))
      (node (ref "U13") (pin "2") (pinfunction "TXD_2") (pintype "output"))
    )
    (net (code "91") (name "TX232-1") (class "Default")
      (node (ref "J5") (pin "5") (pinfunction "5_5") (pintype "passive"))
      (node (ref "R2") (pin "2") (pinfunction "2_2") (pintype "passive"))
      (node (ref "U4") (pin "13") (pinfunction "R1IN_13") (pintype "input"))
    )
    (net (code "92") (name "TX232-2") (class "Default")
      (node (ref "J1") (pin "A5") (pinfunction "A5_A5") (pintype "bidirectional"))
      (node (ref "U6") (pin "13") (pinfunction "R1IN_13") (pintype "input"))
    )
    (net (code "93") (name "TX232-3") (class "Default")
      (node (ref "J1") (pin "B5") (pinfunction "B5_B5") (pintype "bidirectional"))
      (node (ref "U8") (pin "13") (pinfunction "R1IN_13") (pintype "input"))
    )
    (net (code "94") (name "TX232-4") (class "Default")
      (node (ref "J1") (pin "C5") (pinfunction "C5_C5") (pintype "bidirectional"))
      (node (ref "U10") (pin "13") (pinfunction "R1IN_13") (pintype "input"))
    )
    (net (code "95") (name "TX232-5") (class "Default")
      (node (ref "J1") (pin "D5") (pinfunction "D5_D5") (pintype "bidirectional"))
      (node (ref "U12") (pin "13") (pinfunction "R1IN_13") (pintype "input"))
    )
    (net (code "96") (name "UN1") (class "Default")
      (node (ref "U2") (pin "1") (pinfunction "1~{A}_1") (pintype "input"))
      (node (ref "U7") (pin "6") (pinfunction "UD-_6") (pintype "bidirectional"))
    )
    (net (code "97") (name "UN2") (class "Default")
      (node (ref "U2") (pin "3") (pinfunction "1~{CLR}_3") (pintype "input"))
      (node (ref "U9") (pin "6") (pinfunction "UD-_6") (pintype "bidirectional"))
    )
    (net (code "98") (name "UN3") (class "Default")
      (node (ref "U11") (pin "6") (pinfunction "UD-_6") (pintype "bidirectional"))
      (node (ref "U2") (pin "5") (pinfunction "2Q_5") (pintype "output"))
    )
    (net (code "99") (name "UN4") (class "Default")
      (node (ref "U13") (pin "6") (pinfunction "UD-_6") (pintype "bidirectional"))
      (node (ref "U3") (pin "1") (pinfunction "1~{A}_1") (pintype "input"))
    )
    (net (code "100") (name "UN5") (class "Default")
      (node (ref "U3") (pin "3") (pinfunction "1~{CLR}_3") (pintype "input"))
      (node (ref "U5") (pin "6") (pinfunction "UD-_6") (pintype "bidirectional"))
    )
    (net (code "101") (name "UP1") (class "Default")
      (node (ref "U2") (pin "2") (pinfunction "1B_2") (pintype "input"))
      (node (ref "U7") (pin "5") (pinfunction "UD+_5") (pintype "bidirectional"))
    )
    (net (code "102") (name "UP2") (class "Default")
      (node (ref "U2") (pin "4") (pinfunction "1~{Q}_4") (pintype "output"))
      (node (ref "U9") (pin "5") (pinfunction "UD+_5") (pintype "bidirectional"))
    )
    (net (code "103") (name "UP3") (class "Default")
      (node (ref "U11") (pin "5") (pinfunction "UD+_5") (pintype "bidirectional"))
      (node (ref "U2") (pin "6") (pinfunction "2CEXT_6") (pintype "bidirectional"))
    )
    (net (code "104") (name "UP4") (class "Default")
      (node (ref "U13") (pin "5") (pinfunction "UD+_5") (pintype "bidirectional"))
      (node (ref "U3") (pin "2") (pinfunction "1B_2") (pintype "input"))
    )
    (net (code "105") (name "UP5") (class "Default")
      (node (ref "U3") (pin "4") (pinfunction "1~{Q}_4") (pintype "output"))
      (node (ref "U5") (pin "5") (pinfunction "UD+_5") (pintype "bidirectional"))
    )
    (net (code "106") (name "VCC") (class "Default")
      (node (ref "C3") (pin "1") (pinfunction "1_1") (pintype "passive"))
      (node (ref "U1") (pin "13") (pinfunction "1Q_13") (pintype "output"))
      (node (ref "USB2RS1") (pin "1") (pinfunction "1_1") (pintype "bidirectional"))
      (node (ref "USB2RS2") (pin "1") (pinfunction "1_1") (pintype "bidirectional"))
      (node (ref "USB2RS3") (pin "1") (pinfunction "1_1") (pintype "bidirectional"))
      (node (ref "USB2RS5") (pin "1") (pinfunction "1_1") (pintype "bidirectional"))
      (node (ref "X5") (pin "1") (pinfunction "S_1") (pintype "passive"))
      (node (ref "X7") (pin "1") (pinfunction "S_1") (pintype "passive"))
    )
    (net (code "107") (name "unconnected-(J1-PadA1)") (class "Default")
      (node (ref "J1") (pin "A1") (pinfunction "A1_A1") (pintype "bidirectional"))
    )
    (net (code "108") (name "unconnected-(J1-PadA2)") (class "Default")
      (node (ref "J1") (pin "A2") (pinfunction "A2_A2") (pintype "bidirectional"))
    )
    (net (code "109") (name "unconnected-(J1-PadA3)") (class "Default")
      (node (ref "J1") (pin "A3") (pinfunction "A3_A3") (pintype "bidirectional"))
    )
    (net (code "110") (name "unconnected-(J1-PadA6)") (class "Default")
      (node (ref "J1") (pin "A6") (pinfunction "A6_A6") (pintype "bidirectional"))
    )
    (net (code "111") (name "unconnected-(J1-PadA7)") (class "Default")
      (node (ref "J1") (pin "A7") (pinfunction "A7_A7") (pintype "bidirectional"))
    )
    (net (code "112") (name "unconnected-(J1-PadA8)") (class "Default")
      (node (ref "J1") (pin "A8") (pinfunction "A8_A8") (pintype "bidirectional"))
    )
    (net (code "113") (name "unconnected-(J1-PadB1)") (class "Default")
      (node (ref "J1") (pin "B1") (pinfunction "B1_B1") (pintype "bidirectional"))
    )
    (net (code "114") (name "unconnected-(J1-PadB2)") (class "Default")
      (node (ref "J1") (pin "B2") (pinfunction "B2_B2") (pintype "bidirectional"))
    )
    (net (code "115") (name "unconnected-(J1-PadB3)") (class "Default")
      (node (ref "J1") (pin "B3") (pinfunction "B3_B3") (pintype "bidirectional"))
    )
    (net (code "116") (name "unconnected-(J1-PadB6)") (class "Default")
      (node (ref "J1") (pin "B6") (pinfunction "B6_B6") (pintype "bidirectional"))
    )
    (net (code "117") (name "unconnected-(J1-PadB7)") (class "Default")
      (node (ref "J1") (pin "B7") (pinfunction "B7_B7") (pintype "bidirectional"))
    )
    (net (code "118") (name "unconnected-(J1-PadB8)") (class "Default")
      (node (ref "J1") (pin "B8") (pinfunction "B8_B8") (pintype "bidirectional"))
    )
    (net (code "119") (name "unconnected-(J1-PadC1)") (class "Default")
      (node (ref "J1") (pin "C1") (pinfunction "C1_C1") (pintype "bidirectional"))
    )
    (net (code "120") (name "unconnected-(J1-PadC2)") (class "Default")
      (node (ref "J1") (pin "C2") (pinfunction "C2_C2") (pintype "bidirectional"))
    )
    (net (code "121") (name "unconnected-(J1-PadC3)") (class "Default")
      (node (ref "J1") (pin "C3") (pinfunction "C3_C3") (pintype "bidirectional"))
    )
    (net (code "122") (name "unconnected-(J1-PadC6)") (class "Default")
      (node (ref "J1") (pin "C6") (pinfunction "C6_C6") (pintype "bidirectional"))
    )
    (net (code "123") (name "unconnected-(J1-PadC7)") (class "Default")
      (node (ref "J1") (pin "C7") (pinfunction "C7_C7") (pintype "bidirectional"))
    )
    (net (code "124") (name "unconnected-(J1-PadC8)") (class "Default")
      (node (ref "J1") (pin "C8") (pinfunction "C8_C8") (pintype "bidirectional"))
    )
    (net (code "125") (name "unconnected-(J1-PadD1)") (class "Default")
      (node (ref "J1") (pin "D1") (pinfunction "D1_D1") (pintype "bidirectional"))
    )
    (net (code "126") (name "unconnected-(J1-PadD2)") (class "Default")
      (node (ref "J1") (pin "D2") (pinfunction "D2_D2") (pintype "bidirectional"))
    )
    (net (code "127") (name "unconnected-(J1-PadD3)") (class "Default")
      (node (ref "J1") (pin "D3") (pinfunction "D3_D3") (pintype "bidirectional"))
    )
    (net (code "128") (name "unconnected-(J1-PadD6)") (class "Default")
      (node (ref "J1") (pin "D6") (pinfunction "D6_D6") (pintype "bidirectional"))
    )
    (net (code "129") (name "unconnected-(J1-PadD7)") (class "Default")
      (node (ref "J1") (pin "D7") (pinfunction "D7_D7") (pintype "bidirectional"))
    )
    (net (code "130") (name "unconnected-(J1-PadD8)") (class "Default")
      (node (ref "J1") (pin "D8") (pinfunction "D8_D8") (pintype "bidirectional"))
    )
    (net (code "131") (name "unconnected-(J2-PadP1)") (class "Default")
      (node (ref "J2") (pin "P1") (pinfunction "P1_P1") (pintype "passive"))
    )
    (net (code "132") (name "unconnected-(J2-PadP2)") (class "Default")
      (node (ref "J2") (pin "P2") (pinfunction "P2_P2") (pintype "passive"))
    )
    (net (code "133") (name "unconnected-(J2-PadP3)") (class "Default")
      (node (ref "J2") (pin "P3") (pinfunction "P3_P3") (pintype "passive"))
    )
    (net (code "134") (name "unconnected-(J2-PadP4)") (class "Default")
      (node (ref "J2") (pin "P4") (pinfunction "P4_P4") (pintype "passive"))
    )
    (net (code "135") (name "unconnected-(J2-PadP5)") (class "Default")
      (node (ref "J2") (pin "P5") (pinfunction "P5_P5") (pintype "passive"))
    )
    (net (code "136") (name "unconnected-(J2-PadP6)") (class "Default")
      (node (ref "J2") (pin "P6") (pinfunction "P6_P6") (pintype "passive"))
    )
    (net (code "137") (name "unconnected-(J2-PadP7)") (class "Default")
      (node (ref "J2") (pin "P7") (pinfunction "P7_P7") (pintype "passive"))
    )
    (net (code "138") (name "unconnected-(J2-PadP8)") (class "Default")
      (node (ref "J2") (pin "P8") (pinfunction "P8_P8") (pintype "passive"))
    )
    (net (code "139") (name "unconnected-(J5-Pad2)") (class "Default")
      (node (ref "J5") (pin "2") (pinfunction "2_2") (pintype "passive"))
    )
    (net (code "140") (name "unconnected-(J5-Pad3)") (class "Default")
      (node (ref "J5") (pin "3") (pinfunction "3_3") (pintype "passive"))
    )
    (net (code "141") (name "unconnected-(J5-Pad7)") (class "Default")
      (node (ref "J5") (pin "7") (pinfunction "7_7") (pintype "passive"))
    )
    (net (code "142") (name "unconnected-(J5-Pad8)") (class "Default")
      (node (ref "J5") (pin "8") (pinfunction "8_8") (pintype "passive"))
    )
    (net (code "143") (name "unconnected-(U1-1REXT{slash}CEXT-Pad15)") (class "Default")
      (node (ref "U1") (pin "15") (pinfunction "1REXT/CEXT_15") (pintype "bidirectional"))
    )
    (net (code "144") (name "unconnected-(U1-2~{A}-Pad9)") (class "Default")
      (node (ref "U1") (pin "9") (pinfunction "2~{A}_9") (pintype "input"))
    )
    (net (code "145") (name "unconnected-(U1-2~{Q}-Pad12)") (class "Default")
      (node (ref "U1") (pin "12") (pinfunction "2~{Q}_12") (pintype "output"))
    )
    (net (code "146") (name "unconnected-(U2-1REXT{slash}CEXT-Pad15)") (class "Default")
      (node (ref "U2") (pin "15") (pinfunction "1REXT/CEXT_15") (pintype "bidirectional"))
    )
    (net (code "147") (name "unconnected-(U2-2~{A}-Pad9)") (class "Default")
      (node (ref "U2") (pin "9") (pinfunction "2~{A}_9") (pintype "input"))
    )
    (net (code "148") (name "unconnected-(U2-2~{Q}-Pad12)") (class "Default")
      (node (ref "U2") (pin "12") (pinfunction "2~{Q}_12") (pintype "output"))
    )
    (net (code "149") (name "unconnected-(U3-1REXT{slash}CEXT-Pad15)") (class "Default")
      (node (ref "U3") (pin "15") (pinfunction "1REXT/CEXT_15") (pintype "bidirectional"))
    )
    (net (code "150") (name "unconnected-(U3-2CEXT-Pad6)") (class "Default")
      (node (ref "U3") (pin "6") (pinfunction "2CEXT_6") (pintype "bidirectional"))
    )
    (net (code "151") (name "unconnected-(U3-2Q-Pad5)") (class "Default")
      (node (ref "U3") (pin "5") (pinfunction "2Q_5") (pintype "output"))
    )
    (net (code "152") (name "unconnected-(U3-2REXT{slash}CEXT-Pad7)") (class "Default")
      (node (ref "U3") (pin "7") (pinfunction "2REXT/CEXT_7") (pintype "bidirectional"))
    )
    (net (code "153") (name "unconnected-(U3-2~{A}-Pad9)") (class "Default")
      (node (ref "U3") (pin "9") (pinfunction "2~{A}_9") (pintype "input"))
    )
    (net (code "154") (name "unconnected-(U3-2~{Q}-Pad12)") (class "Default")
      (node (ref "U3") (pin "12") (pinfunction "2~{Q}_12") (pintype "output"))
    )
    (net (code "155") (name "unconnected-(U3-GND-Pad8)") (class "Default")
      (node (ref "U3") (pin "8") (pinfunction "GND_8") (pintype "power_in"))
    )
    (net (code "156") (name "unconnected-(U4-R2IN-Pad8)") (class "Default")
      (node (ref "U4") (pin "8") (pinfunction "R2IN_8") (pintype "input"))
    )
    (net (code "157") (name "unconnected-(U4-R2OUT-Pad9)") (class "Default")
      (node (ref "U4") (pin "9") (pinfunction "R2OUT_9") (pintype "output"))
    )
    (net (code "158") (name "unconnected-(U4-T2IN-Pad10)") (class "Default")
      (node (ref "U4") (pin "10") (pinfunction "T2IN_10") (pintype "input"))
    )
    (net (code "159") (name "unconnected-(U4-T2OUT-Pad7)") (class "Default")
      (node (ref "U4") (pin "7") (pinfunction "T2OUT_7") (pintype "output"))
    )
    (net (code "160") (name "unconnected-(U5-RS232-Pad15)") (class "Default")
      (node (ref "U5") (pin "15") (pinfunction "RS232_15") (pintype "input"))
    )
    (net (code "161") (name "unconnected-(U5-XI-Pad7)") (class "Default")
      (node (ref "U5") (pin "7") (pinfunction "XI_7") (pintype "input"))
    )
    (net (code "162") (name "unconnected-(U5-XO-Pad8)") (class "Default")
      (node (ref "U5") (pin "8") (pinfunction "XO_8") (pintype "output"))
    )
    (net (code "163") (name "unconnected-(U5-~{CTS}-Pad9)") (class "Default")
      (node (ref "U5") (pin "9") (pinfunction "~{CTS}_9") (pintype "input"))
    )
    (net (code "164") (name "unconnected-(U5-~{DCD}-Pad12)") (class "Default")
      (node (ref "U5") (pin "12") (pinfunction "~{DCD}_12") (pintype "input"))
    )
    (net (code "165") (name "unconnected-(U5-~{DSR}-Pad10)") (class "Default")
      (node (ref "U5") (pin "10") (pinfunction "~{DSR}_10") (pintype "input"))
    )
    (net (code "166") (name "unconnected-(U5-~{DTR}-Pad13)") (class "Default")
      (node (ref "U5") (pin "13") (pinfunction "~{DTR}_13") (pintype "output"))
    )
    (net (code "167") (name "unconnected-(U5-~{RI}-Pad11)") (class "Default")
      (node (ref "U5") (pin "11") (pinfunction "~{RI}_11") (pintype "input"))
    )
    (net (code "168") (name "unconnected-(U5-~{RTS}-Pad14)") (class "Default")
      (node (ref "U5") (pin "14") (pinfunction "~{RTS}_14") (pintype "output"))
    )
    (net (code "169") (name "unconnected-(U6-R2IN-Pad8)") (class "Default")
      (node (ref "U6") (pin "8") (pinfunction "R2IN_8") (pintype "input"))
    )
    (net (code "170") (name "unconnected-(U6-R2OUT-Pad9)") (class "Default")
      (node (ref "U6") (pin "9") (pinfunction "R2OUT_9") (pintype "output"))
    )
    (net (code "171") (name "unconnected-(U6-T2IN-Pad10)") (class "Default")
      (node (ref "U6") (pin "10") (pinfunction "T2IN_10") (pintype "input"))
    )
    (net (code "172") (name "unconnected-(U6-T2OUT-Pad7)") (class "Default")
      (node (ref "U6") (pin "7") (pinfunction "T2OUT_7") (pintype "output"))
    )
    (net (code "173") (name "unconnected-(U7-RS232-Pad15)") (class "Default")
      (node (ref "U7") (pin "15") (pinfunction "RS232_15") (pintype "input"))
    )
    (net (code "174") (name "unconnected-(U7-XI-Pad7)") (class "Default")
      (node (ref "U7") (pin "7") (pinfunction "XI_7") (pintype "input"))
    )
    (net (code "175") (name "unconnected-(U7-XO-Pad8)") (class "Default")
      (node (ref "U7") (pin "8") (pinfunction "XO_8") (pintype "output"))
    )
    (net (code "176") (name "unconnected-(U7-~{CTS}-Pad9)") (class "Default")
      (node (ref "U7") (pin "9") (pinfunction "~{CTS}_9") (pintype "input"))
    )
    (net (code "177") (name "unconnected-(U7-~{DCD}-Pad12)") (class "Default")
      (node (ref "U7") (pin "12") (pinfunction "~{DCD}_12") (pintype "input"))
    )
    (net (code "178") (name "unconnected-(U7-~{DSR}-Pad10)") (class "Default")
      (node (ref "U7") (pin "10") (pinfunction "~{DSR}_10") (pintype "input"))
    )
    (net (code "179") (name "unconnected-(U7-~{DTR}-Pad13)") (class "Default")
      (node (ref "U7") (pin "13") (pinfunction "~{DTR}_13") (pintype "output"))
    )
    (net (code "180") (name "unconnected-(U7-~{RI}-Pad11)") (class "Default")
      (node (ref "U7") (pin "11") (pinfunction "~{RI}_11") (pintype "input"))
    )
    (net (code "181") (name "unconnected-(U7-~{RTS}-Pad14)") (class "Default")
      (node (ref "U7") (pin "14") (pinfunction "~{RTS}_14") (pintype "output"))
    )
    (net (code "182") (name "unconnected-(U8-R2IN-Pad8)") (class "Default")
      (node (ref "U8") (pin "8") (pinfunction "R2IN_8") (pintype "input"))
    )
    (net (code "183") (name "unconnected-(U8-R2OUT-Pad9)") (class "Default")
      (node (ref "U8") (pin "9") (pinfunction "R2OUT_9") (pintype "output"))
    )
    (net (code "184") (name "unconnected-(U8-T2IN-Pad10)") (class "Default")
      (node (ref "U8") (pin "10") (pinfunction "T2IN_10") (pintype "input"))
    )
    (net (code "185") (name "unconnected-(U8-T2OUT-Pad7)") (class "Default")
      (node (ref "U8") (pin "7") (pinfunction "T2OUT_7") (pintype "output"))
    )
    (net (code "186") (name "unconnected-(U9-RS232-Pad15)") (class "Default")
      (node (ref "U9") (pin "15") (pinfunction "RS232_15") (pintype "input"))
    )
    (net (code "187") (name "unconnected-(U9-XI-Pad7)") (class "Default")
      (node (ref "U9") (pin "7") (pinfunction "XI_7") (pintype "input"))
    )
    (net (code "188") (name "unconnected-(U9-XO-Pad8)") (class "Default")
      (node (ref "U9") (pin "8") (pinfunction "XO_8") (pintype "output"))
    )
    (net (code "189") (name "unconnected-(U9-~{CTS}-Pad9)") (class "Default")
      (node (ref "U9") (pin "9") (pinfunction "~{CTS}_9") (pintype "input"))
    )
    (net (code "190") (name "unconnected-(U9-~{DCD}-Pad12)") (class "Default")
      (node (ref "U9") (pin "12") (pinfunction "~{DCD}_12") (pintype "input"))
    )
    (net (code "191") (name "unconnected-(U9-~{DSR}-Pad10)") (class "Default")
      (node (ref "U9") (pin "10") (pinfunction "~{DSR}_10") (pintype "input"))
    )
    (net (code "192") (name "unconnected-(U9-~{DTR}-Pad13)") (class "Default")
      (node (ref "U9") (pin "13") (pinfunction "~{DTR}_13") (pintype "output"))
    )
    (net (code "193") (name "unconnected-(U9-~{RI}-Pad11)") (class "Default")
      (node (ref "U9") (pin "11") (pinfunction "~{RI}_11") (pintype "input"))
    )
    (net (code "194") (name "unconnected-(U9-~{RTS}-Pad14)") (class "Default")
      (node (ref "U9") (pin "14") (pinfunction "~{RTS}_14") (pintype "output"))
    )
    (net (code "195") (name "unconnected-(U10-R2IN-Pad8)") (class "Default")
      (node (ref "U10") (pin "8") (pinfunction "R2IN_8") (pintype "input"))
    )
    (net (code "196") (name "unconnected-(U10-R2OUT-Pad9)") (class "Default")
      (node (ref "U10") (pin "9") (pinfunction "R2OUT_9") (pintype "output"))
    )
    (net (code "197") (name "unconnected-(U10-T2IN-Pad10)") (class "Default")
      (node (ref "U10") (pin "10") (pinfunction "T2IN_10") (pintype "input"))
    )
    (net (code "198") (name "unconnected-(U10-T2OUT-Pad7)") (class "Default")
      (node (ref "U10") (pin "7") (pinfunction "T2OUT_7") (pintype "output"))
    )
    (net (code "199") (name "unconnected-(U11-RS232-Pad15)") (class "Default")
      (node (ref "U11") (pin "15") (pinfunction "RS232_15") (pintype "input"))
    )
    (net (code "200") (name "unconnected-(U11-XI-Pad7)") (class "Default")
      (node (ref "U11") (pin "7") (pinfunction "XI_7") (pintype "input"))
    )
    (net (code "201") (name "unconnected-(U11-XO-Pad8)") (class "Default")
      (node (ref "U11") (pin "8") (pinfunction "XO_8") (pintype "output"))
    )
    (net (code "202") (name "unconnected-(U11-~{CTS}-Pad9)") (class "Default")
      (node (ref "U11") (pin "9") (pinfunction "~{CTS}_9") (pintype "input"))
    )
    (net (code "203") (name "unconnected-(U11-~{DCD}-Pad12)") (class "Default")
      (node (ref "U11") (pin "12") (pinfunction "~{DCD}_12") (pintype "input"))
    )
    (net (code "204") (name "unconnected-(U11-~{DSR}-Pad10)") (class "Default")
      (node (ref "U11") (pin "10") (pinfunction "~{DSR}_10") (pintype "input"))
    )
    (net (code "205") (name "unconnected-(U11-~{DTR}-Pad13)") (class "Default")
      (node (ref "U11") (pin "13") (pinfunction "~{DTR}_13") (pintype "output"))
    )
    (net (code "206") (name "unconnected-(U11-~{RI}-Pad11)") (class "Default")
      (node (ref "U11") (pin "11") (pinfunction "~{RI}_11") (pintype "input"))
    )
    (net (code "207") (name "unconnected-(U11-~{RTS}-Pad14)") (class "Default")
      (node (ref "U11") (pin "14") (pinfunction "~{RTS}_14") (pintype "output"))
    )
    (net (code "208") (name "unconnected-(U12-R2IN-Pad8)") (class "Default")
      (node (ref "U12") (pin "8") (pinfunction "R2IN_8") (pintype "input"))
    )
    (net (code "209") (name "unconnected-(U12-R2OUT-Pad9)") (class "Default")
      (node (ref "U12") (pin "9") (pinfunction "R2OUT_9") (pintype "output"))
    )
    (net (code "210") (name "unconnected-(U12-T2IN-Pad10)") (class "Default")
      (node (ref "U12") (pin "10") (pinfunction "T2IN_10") (pintype "input"))
    )
    (net (code "211") (name "unconnected-(U12-T2OUT-Pad7)") (class "Default")
      (node (ref "U12") (pin "7") (pinfunction "T2OUT_7") (pintype "output"))
    )
    (net (code "212") (name "unconnected-(U13-RS232-Pad15)") (class "Default")
      (node (ref "U13") (pin "15") (pinfunction "RS232_15") (pintype "input"))
    )
    (net (code "213") (name "unconnected-(U13-XI-Pad7)") (class "Default")
      (node (ref "U13") (pin "7") (pinfunction "XI_7") (pintype "input"))
    )
    (net (code "214") (name "unconnected-(U13-XO-Pad8)") (class "Default")
      (node (ref "U13") (pin "8") (pinfunction "XO_8") (pintype "output"))
    )
    (net (code "215") (name "unconnected-(U13-~{CTS}-Pad9)") (class "Default")
      (node (ref "U13") (pin "9") (pinfunction "~{CTS}_9") (pintype "input"))
    )
    (net (code "216") (name "unconnected-(U13-~{DCD}-Pad12)") (class "Default")
      (node (ref "U13") (pin "12") (pinfunction "~{DCD}_12") (pintype "input"))
    )
    (net (code "217") (name "unconnected-(U13-~{DSR}-Pad10)") (class "Default")
      (node (ref "U13") (pin "10") (pinfunction "~{DSR}_10") (pintype "input"))
    )
    (net (code "218") (name "unconnected-(U13-~{DTR}-Pad13)") (class "Default")
      (node (ref "U13") (pin "13") (pinfunction "~{DTR}_13") (pintype "output"))
    )
    (net (code "219") (name "unconnected-(U13-~{RI}-Pad11)") (class "Default")
      (node (ref "U13") (pin "11") (pinfunction "~{RI}_11") (pintype "input"))
    )
    (net (code "220") (name "unconnected-(U13-~{RTS}-Pad14)") (class "Default")
      (node (ref "U13") (pin "14") (pinfunction "~{RTS}_14") (pintype "output"))
    )
  )
)
